# openlrsng.net
KiCad netlist of a schematic drawn in EAGLE
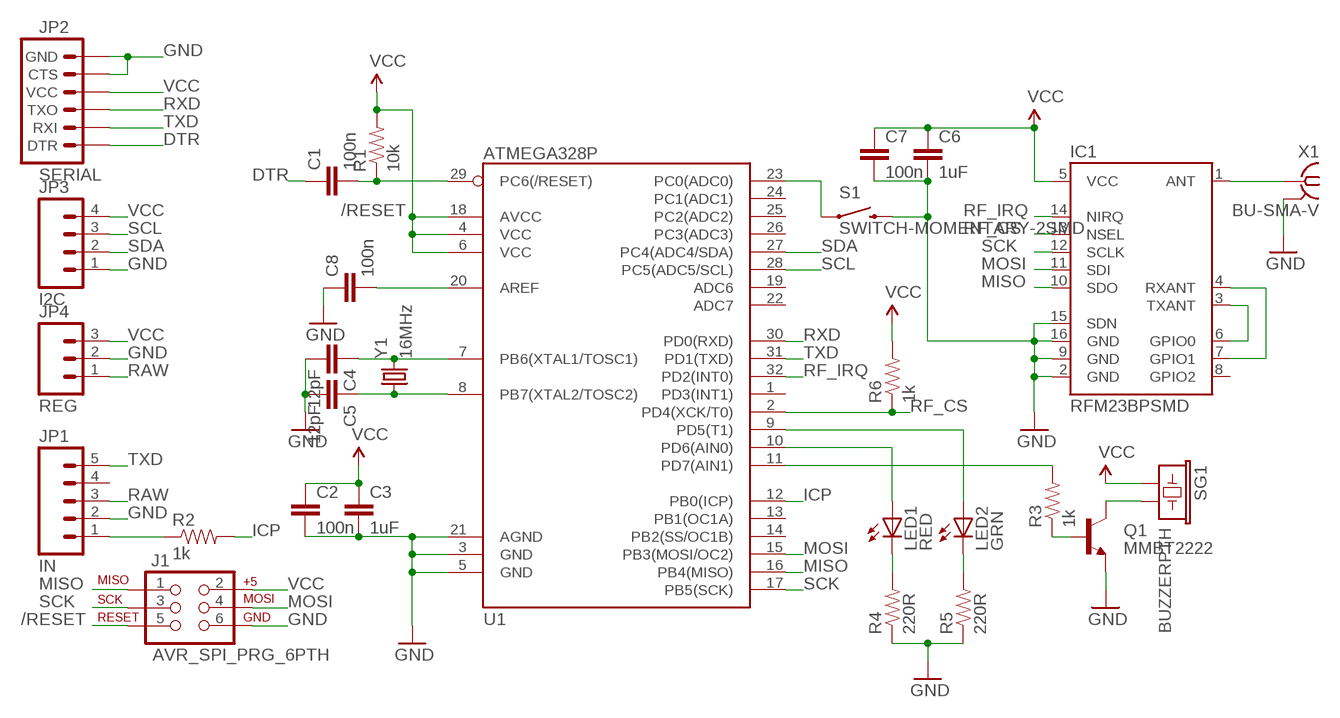
[diagram p0: schematic, sheet 1]

(export (version "E")
  (design (tool "Eeschema 10.0.6"))
  (components
    (comp (ref "C1")
      (value "100n")
      (footprint "eagle-import:0805")
      (libsource (lib "eagle-import") (part "CAP0805"))
    )
    (comp (ref "C2")
      (value "100n")
      (footprint "eagle-import:0805")
      (libsource (lib "eagle-import") (part "CAP0805"))
    )
    (comp (ref "C3")
      (value "1uF")
      (footprint "eagle-import:0805")
      (libsource (lib "eagle-import") (part "CAP0805"))
    )
    (comp (ref "C4")
      (value "12pF")
      (footprint "eagle-import:0805")
      (libsource (lib "eagle-import") (part "CAP0805"))
    )
    (comp (ref "C5")
      (value "12pF")
      (footprint "eagle-import:0805")
      (libsource (lib "eagle-import") (part "CAP0805"))
    )
    (comp (ref "C6")
      (value "1uF")
      (footprint "eagle-import:0805")
      (libsource (lib "eagle-import") (part "CAP0805"))
    )
    (comp (ref "C7")
      (value "100n")
      (footprint "eagle-import:0805")
      (libsource (lib "eagle-import") (part "CAP0805"))
    )
    (comp (ref "C8")
      (value "100n")
      (footprint "eagle-import:0805")
      (libsource (lib "eagle-import") (part "CAP0805"))
    )
    (comp (ref "IC1")
      (value "RFM23BPSMD")
      (footprint "eagle-import:RFM23BP-S2")
      (libsource (lib "eagle-import") (part "RFM23BPSMD"))
    )
    (comp (ref "J1")
      (value "AVR_SPI_PRG_6PTH")
      (footprint "eagle-import:2X3")
      (libsource (lib "eagle-import") (part "AVR_SPI_PRG_6PTH"))
    )
    (comp (ref "JP1")
      (value "IN")
      (footprint "eagle-import:1X05")
      (libsource (lib "eagle-import") (part "M05PTH"))
    )
    (comp (ref "JP2")
      (value "SERIAL")
      (footprint "eagle-import:1X06")
      (libsource (lib "eagle-import") (part "ARDUINO_SERIAL_PROGRAMPTH"))
    )
    (comp (ref "JP3")
      (value "I2C")
      (footprint "eagle-import:1X04")
      (libsource (lib "eagle-import") (part "M04PTH"))
    )
    (comp (ref "JP4")
      (value "REG")
      (footprint "eagle-import:1X03")
      (libsource (lib "eagle-import") (part "M03PTH"))
    )
    (comp (ref "LED1")
      (value "RED")
      (footprint "eagle-import:LED3MM")
      (libsource (lib "eagle-import") (part "LED3MM"))
    )
    (comp (ref "LED2")
      (value "GRN")
      (footprint "eagle-import:LED3MM")
      (libsource (lib "eagle-import") (part "LED3MM"))
    )
    (comp (ref "Q1")
      (value "MMBT2222")
      (footprint "eagle-import:SOT23-3")
      (libsource (lib "eagle-import") (part "TRANSISTOR_NPNSOT23-3"))
    )
    (comp (ref "R1")
      (value "10k")
      (footprint "eagle-import:0402-RES")
      (libsource (lib "eagle-import") (part "RESISTOR0402-RES"))
    )
    (comp (ref "R2")
      (value "1k")
      (footprint "eagle-import:0402-RES")
      (libsource (lib "eagle-import") (part "RESISTOR0402-RES"))
    )
    (comp (ref "R3")
      (value "1k")
      (footprint "eagle-import:0402-RES")
      (libsource (lib "eagle-import") (part "RESISTOR0402-RES"))
    )
    (comp (ref "R4")
      (value "220R")
      (footprint "eagle-import:0402-RES")
      (libsource (lib "eagle-import") (part "RESISTOR0402-RES"))
    )
    (comp (ref "R5")
      (value "220R")
      (footprint "eagle-import:0402-RES")
      (libsource (lib "eagle-import") (part "RESISTOR0402-RES"))
    )
    (comp (ref "R6")
      (value "1k")
      (footprint "eagle-import:0402-RES")
      (libsource (lib "eagle-import") (part "RESISTOR0402-RES"))
    )
    (comp (ref "S1")
      (value "SWITCH-MOMENTARY-2SMD")
      (footprint "eagle-import:TACTILE_SWITCH_SMD")
      (libsource (lib "eagle-import") (part "SWITCH-MOMENTARY-2SMD"))
    )
    (comp (ref "SG1")
      (value "BUZZERPTH")
      (footprint "eagle-import:BUZZER-12MM")
      (libsource (lib "eagle-import") (part "BUZZERPTH"))
    )
    (comp (ref "U1")
      (value "ATMEGA328P")
      (footprint "eagle-import:TQFP32-08")
      (libsource (lib "eagle-import") (part "ATMEGA328_SMT"))
    )
    (comp (ref "X1")
      (value "BU-SMA-V")
      (footprint "eagle-import:BU-SMA-V")
      (libsource (lib "eagle-import") (part "BU-SMA-V"))
    )
    (comp (ref "Y1")
      (value "16MHz")
      (footprint "eagle-import:CRYSTAL-SMD-5X3")
      (libsource (lib "eagle-import") (part "CRYSTAL3.2X2.5"))
    )
  )
  (nets
    (net (code "1") (name "/DTR") (class "Default")
      (node (ref "C1") (pin "1") (pinfunction "1_1") (pintype "passive"))
      (node (ref "JP2") (pin "1") (pinfunction "DTR_1") (pintype "passive"))
    )
    (net (code "2") (name "/ICP") (class "Default")
      (node (ref "R2") (pin "2") (pinfunction "2_2") (pintype "passive"))
      (node (ref "U1") (pin "12") (pinfunction "PB0(ICP)_12") (pintype "bidirectional"))
    )
    (net (code "3") (name "/MISO") (class "Default")
      (node (ref "IC1") (pin "10") (pinfunction "SDO_10") (pintype "output"))
      (node (ref "J1") (pin "1") (pinfunction "1_1") (pintype "passive"))
      (node (ref "U1") (pin "16") (pinfunction "PB4(MISO)_16") (pintype "bidirectional"))
    )
    (net (code "4") (name "/MOSI") (class "Default")
      (node (ref "IC1") (pin "11") (pinfunction "SDI_11") (pintype "input"))
      (node (ref "J1") (pin "4") (pinfunction "4_4") (pintype "passive"))
      (node (ref "U1") (pin "15") (pinfunction "PB3(MOSI/OC2)_15") (pintype "bidirectional"))
    )
    (net (code "5") (name "/RAW") (class "Default")
      (node (ref "JP1") (pin "3") (pinfunction "3_3") (pintype "passive"))
      (node (ref "JP4") (pin "1") (pinfunction "1_1") (pintype "passive"))
    )
    (net (code "6") (name "/RF_CS") (class "Default")
      (node (ref "IC1") (pin "13") (pinfunction "NSEL_13") (pintype "input"))
      (node (ref "R6") (pin "1") (pinfunction "1_1") (pintype "passive"))
      (node (ref "U1") (pin "2") (pinfunction "PD4(XCK/T0)_2") (pintype "bidirectional"))
    )
    (net (code "7") (name "/RF_IRQ") (class "Default")
      (node (ref "IC1") (pin "14") (pinfunction "NIRQ_14") (pintype "output"))
      (node (ref "U1") (pin "32") (pinfunction "PD2(INT0)_32") (pintype "bidirectional"))
    )
    (net (code "8") (name "/RXD") (class "Default")
      (node (ref "JP2") (pin "3") (pinfunction "TXO_3") (pintype "passive"))
      (node (ref "U1") (pin "30") (pinfunction "PD0(RXD)_30") (pintype "bidirectional"))
    )
    (net (code "9") (name "/SCK") (class "Default")
      (node (ref "IC1") (pin "12") (pinfunction "SCLK_12") (pintype "input"))
      (node (ref "J1") (pin "3") (pinfunction "3_3") (pintype "passive"))
      (node (ref "U1") (pin "17") (pinfunction "PB5(SCK)_17") (pintype "bidirectional"))
    )
    (net (code "10") (name "/SCL") (class "Default")
      (node (ref "JP3") (pin "3") (pinfunction "3_3") (pintype "passive"))
      (node (ref "U1") (pin "28") (pinfunction "PC5(ADC5/SCL)_28") (pintype "bidirectional"))
    )
    (net (code "11") (name "/SDA") (class "Default")
      (node (ref "JP3") (pin "2") (pinfunction "2_2") (pintype "passive"))
      (node (ref "U1") (pin "27") (pinfunction "PC4(ADC4/SDA)_27") (pintype "bidirectional"))
    )
    (net (code "12") (name "/TXD") (class "Default")
      (node (ref "JP1") (pin "5") (pinfunction "5_5") (pintype "passive"))
      (node (ref "JP2") (pin "2") (pinfunction "RXI_2") (pintype "passive"))
      (node (ref "U1") (pin "31") (pinfunction "PD1(TXD)_31") (pintype "bidirectional"))
    )
    (net (code "13") (name "/{slash}RESET") (class "Default")
      (node (ref "C1") (pin "2") (pinfunction "2_2") (pintype "passive"))
      (node (ref "J1") (pin "5") (pinfunction "5_5") (pintype "passive"))
      (node (ref "R1") (pin "1") (pinfunction "1_1") (pintype "passive"))
      (node (ref "U1") (pin "29") (pinfunction "PC6(/RESET)_29") (pintype "bidirectional"))
    )
    (net (code "14") (name "GND") (class "Default")
      (node (ref "C2") (pin "2") (pinfunction "2_2") (pintype "passive"))
      (node (ref "C3") (pin "2") (pinfunction "2_2") (pintype "passive"))
      (node (ref "C4") (pin "2") (pinfunction "2_2") (pintype "passive"))
      (node (ref "C5") (pin "2") (pinfunction "2_2") (pintype "passive"))
      (node (ref "C6") (pin "2") (pinfunction "2_2") (pintype "passive"))
      (node (ref "C7") (pin "2") (pinfunction "2_2") (pintype "passive"))
      (node (ref "C8") (pin "1") (pinfunction "1_1") (pintype "passive"))
      (node (ref "IC1") (pin "15") (pinfunction "SDN_15") (pintype "input"))
      (node (ref "IC1") (pin "16") (pinfunction "GND_16") (pintype "power_in"))
      (node (ref "IC1") (pin "2") (pinfunction "GND_2") (pintype "power_in"))
      (node (ref "IC1") (pin "9") (pinfunction "GND_9") (pintype "power_in"))
      (node (ref "J1") (pin "6") (pinfunction "6_6") (pintype "passive"))
      (node (ref "JP1") (pin "2") (pinfunction "2_2") (pintype "passive"))
      (node (ref "JP2") (pin "5") (pinfunction "CTS_5") (pintype "passive"))
      (node (ref "JP2") (pin "6") (pinfunction "GND_6") (pintype "passive"))
      (node (ref "JP3") (pin "1") (pinfunction "1_1") (pintype "passive"))
      (node (ref "JP4") (pin "2") (pinfunction "2_2") (pintype "passive"))
      (node (ref "Q1") (pin "2") (pinfunction "E_2") (pintype "passive"))
      (node (ref "R4") (pin "1") (pinfunction "1_1") (pintype "passive"))
      (node (ref "R5") (pin "1") (pinfunction "1_1") (pintype "passive"))
      (node (ref "S1") (pin "3") (pinfunction "2_3") (pintype "passive"))
      (node (ref "U1") (pin "21") (pinfunction "AGND_21") (pintype "bidirectional"))
      (node (ref "U1") (pin "3") (pinfunction "GND_3") (pintype "bidirectional"))
      (node (ref "U1") (pin "5") (pinfunction "GND_5") (pintype "bidirectional"))
      (node (ref "X1") (pin "2") (pinfunction "2_2") (pintype "passive"))
      (node (ref "X1") (pin "3") (pinfunction "2_3") (pintype "passive"))
      (node (ref "X1") (pin "4") (pinfunction "2_4") (pintype "passive"))
      (node (ref "X1") (pin "5") (pinfunction "2_5") (pintype "passive"))
    )
    (net (code "15") (name "Net-(IC1-ANT)") (class "Default")
      (node (ref "IC1") (pin "1") (pinfunction "ANT_1") (pintype "bidirectional"))
      (node (ref "X1") (pin "1") (pinfunction "1_1") (pintype "passive"))
    )
    (net (code "16") (name "Net-(IC1-GPIO0)") (class "Default")
      (node (ref "IC1") (pin "3") (pinfunction "TXANT_3") (pintype "input"))
      (node (ref "IC1") (pin "6") (pinfunction "GPIO0_6") (pintype "bidirectional"))
    )
    (net (code "17") (name "Net-(IC1-GPIO1)") (class "Default")
      (node (ref "IC1") (pin "4") (pinfunction "RXANT_4") (pintype "input"))
      (node (ref "IC1") (pin "7") (pinfunction "GPIO1_7") (pintype "bidirectional"))
    )
    (net (code "18") (name "Net-(JP1-Pad1)") (class "Default")
      (node (ref "JP1") (pin "1") (pinfunction "1_1") (pintype "passive"))
      (node (ref "R2") (pin "1") (pinfunction "1_1") (pintype "passive"))
    )
    (net (code "19") (name "Net-(LED1-C)") (class "Default")
      (node (ref "LED1") (pin "K") (pinfunction "C_K") (pintype "passive"))
      (node (ref "R4") (pin "2") (pinfunction "2_2") (pintype "passive"))
    )
    (net (code "20") (name "Net-(LED2-C)") (class "Default")
      (node (ref "LED2") (pin "K") (pinfunction "C_K") (pintype "passive"))
      (node (ref "R5") (pin "2") (pinfunction "2_2") (pintype "passive"))
    )
    (net (code "21") (name "Net-(Q1-B)") (class "Default")
      (node (ref "Q1") (pin "1") (pinfunction "B_1") (pintype "passive"))
      (node (ref "R3") (pin "1") (pinfunction "1_1") (pintype "passive"))
    )
    (net (code "22") (name "Net-(Q1-C)") (class "Default")
      (node (ref "Q1") (pin "3") (pinfunction "C_3") (pintype "passive"))
      (node (ref "SG1") (pin "-") (pinfunction "2_-") (pintype "passive"))
    )
    (net (code "23") (name "Net-(U1-AREF)") (class "Default")
      (node (ref "C8") (pin "2") (pinfunction "2_2") (pintype "passive"))
      (node (ref "U1") (pin "20") (pinfunction "AREF_20") (pintype "bidirectional"))
    )
    (net (code "24") (name "Net-(U1-PB6(XTAL1{slash}TOSC1))") (class "Default")
      (node (ref "C4") (pin "1") (pinfunction "1_1") (pintype "passive"))
      (node (ref "U1") (pin "7") (pinfunction "PB6(XTAL1/TOSC1)_7") (pintype "bidirectional"))
      (node (ref "Y1") (pin "3") (pinfunction "2_3") (pintype "passive"))
    )
    (net (code "25") (name "Net-(U1-PB7(XTAL2{slash}TOSC2))") (class "Default")
      (node (ref "C5") (pin "1") (pinfunction "1_1") (pintype "passive"))
      (node (ref "U1") (pin "8") (pinfunction "PB7(XTAL2/TOSC2)_8") (pintype "bidirectional"))
      (node (ref "Y1") (pin "1") (pinfunction "1_1") (pintype "passive"))
    )
    (net (code "26") (name "Net-(U1-PC0(ADC0))") (class "Default")
      (node (ref "S1") (pin "1") (pinfunction "1_1") (pintype "passive"))
      (node (ref "U1") (pin "23") (pinfunction "PC0(ADC0)_23") (pintype "bidirectional"))
    )
    (net (code "27") (name "Net-(U1-PD5(T1))") (class "Default")
      (node (ref "LED2") (pin "A") (pinfunction "A_A") (pintype "passive"))
      (node (ref "U1") (pin "9") (pinfunction "PD5(T1)_9") (pintype "bidirectional"))
    )
    (net (code "28") (name "Net-(U1-PD6(AIN0))") (class "Default")
      (node (ref "LED1") (pin "A") (pinfunction "A_A") (pintype "passive"))
      (node (ref "U1") (pin "10") (pinfunction "PD6(AIN0)_10") (pintype "bidirectional"))
    )
    (net (code "29") (name "Net-(U1-PD7(AIN1))") (class "Default")
      (node (ref "R3") (pin "2") (pinfunction "2_2") (pintype "passive"))
      (node (ref "U1") (pin "11") (pinfunction "PD7(AIN1)_11") (pintype "bidirectional"))
    )
    (net (code "30") (name "VCC") (class "Default")
      (node (ref "C2") (pin "1") (pinfunction "1_1") (pintype "passive"))
      (node (ref "C3") (pin "1") (pinfunction "1_1") (pintype "passive"))
      (node (ref "C6") (pin "1") (pinfunction "1_1") (pintype "passive"))
      (node (ref "C7") (pin "1") (pinfunction "1_1") (pintype "passive"))
      (node (ref "IC1") (pin "5") (pinfunction "VCC_5") (pintype "bidirectional"))
      (node (ref "J1") (pin "2") (pinfunction "2_2") (pintype "passive"))
      (node (ref "JP2") (pin "4") (pinfunction "VCC_4") (pintype "passive"))
      (node (ref "JP3") (pin "4") (pinfunction "4_4") (pintype "passive"))
      (node (ref "JP4") (pin "3") (pinfunction "3_3") (pintype "passive"))
      (node (ref "R1") (pin "2") (pinfunction "2_2") (pintype "passive"))
      (node (ref "R6") (pin "2") (pinfunction "2_2") (pintype "passive"))
      (node (ref "SG1") (pin "+") (pinfunction "1_+") (pintype "passive"))
      (node (ref "U1") (pin "18") (pinfunction "AVCC_18") (pintype "bidirectional"))
      (node (ref "U1") (pin "4") (pinfunction "VCC_4") (pintype "bidirectional"))
      (node (ref "U1") (pin "6") (pinfunction "VCC_6") (pintype "bidirectional"))
    )
    (net (code "31") (name "unconnected-(IC1-GPIO2-Pad8)") (class "Default")
      (node (ref "IC1") (pin "8") (pinfunction "GPIO2_8") (pintype "bidirectional"))
    )
    (net (code "32") (name "unconnected-(JP1-Pad4)") (class "Default")
      (node (ref "JP1") (pin "4") (pinfunction "4_4") (pintype "passive"))
    )
    (net (code "33") (name "unconnected-(U1-ADC6-Pad19)") (class "Default")
      (node (ref "U1") (pin "19") (pinfunction "ADC6_19") (pintype "bidirectional"))
    )
    (net (code "34") (name "unconnected-(U1-ADC7-Pad22)") (class "Default")
      (node (ref "U1") (pin "22") (pinfunction "ADC7_22") (pintype "bidirectional"))
    )
    (net (code "35") (name "unconnected-(U1-PB1(OC1A)-Pad13)") (class "Default")
      (node (ref "U1") (pin "13") (pinfunction "PB1(OC1A)_13") (pintype "bidirectional"))
    )
    (net (code "36") (name "unconnected-(U1-PB2(SS{slash}OC1B)-Pad14)") (class "Default")
      (node (ref "U1") (pin "14") (pinfunction "PB2(SS/OC1B)_14") (pintype "bidirectional"))
    )
    (net (code "37") (name "unconnected-(U1-PC1(ADC1)-Pad24)") (class "Default")
      (node (ref "U1") (pin "24") (pinfunction "PC1(ADC1)_24") (pintype "bidirectional"))
    )
    (net (code "38") (name "unconnected-(U1-PC2(ADC2)-Pad25)") (class "Default")
      (node (ref "U1") (pin "25") (pinfunction "PC2(ADC2)_25") (pintype "bidirectional"))
    )
    (net (code "39") (name "unconnected-(U1-PC3(ADC3)-Pad26)") (class "Default")
      (node (ref "U1") (pin "26") (pinfunction "PC3(ADC3)_26") (pintype "bidirectional"))
    )
    (net (code "40") (name "unconnected-(U1-PD3(INT1)-Pad1)") (class "Default")
      (node (ref "U1") (pin "1") (pinfunction "PD3(INT1)_1") (pintype "bidirectional"))
    )
  )
)
